# Motors.net
KiCad netlist of a schematic drawn in Altium Designer
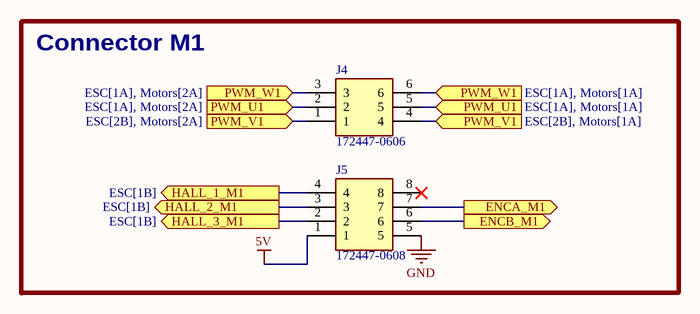
[diagram p0: Motors.SchDoc]

(export (version "E")
  (design (tool "Eeschema 10.0.6"))
  (components
    (comp (ref "J4")
      (value "172447-0606")
      (footprint "roboime:172447-YY06")
      (description "Connector")
      (fields (field (name "MOUSER PART NUMBER") "538-172447-0606"))
      (libsource (lib "roboime") (part "172447-0606"))
    )
    (comp (ref "J5")
      (value "172447-0608")
      (footprint "roboime:172447-YY08")
      (description "Connector Mate 46992-0840")
      (fields (field (name "MOUSER PART NUMBER") "538-172447-0608"))
      (libsource (lib "roboime") (part "172447-0608"))
    )
  )
  (nets
    (net (code "1") (name "/ENCA_M1") (class "Default")
      (node (ref "J5") (pin "7") (pinfunction "7_7") (pintype "passive"))
    )
    (net (code "2") (name "/ENCB_M1") (class "Default")
      (node (ref "J5") (pin "6") (pinfunction "6_6") (pintype "passive"))
    )
    (net (code "3") (name "/HALL_1_M1") (class "Default")
      (node (ref "J5") (pin "4") (pinfunction "4_4") (pintype "passive"))
    )
    (net (code "4") (name "/HALL_2_M1") (class "Default")
      (node (ref "J5") (pin "3") (pinfunction "3_3") (pintype "passive"))
    )
    (net (code "5") (name "/HALL_3_M1") (class "Default")
      (node (ref "J5") (pin "2") (pinfunction "2_2") (pintype "passive"))
    )
    (net (code "6") (name "/PWM_U1") (class "Default")
      (node (ref "J4") (pin "2") (pinfunction "2_2") (pintype "passive"))
      (node (ref "J4") (pin "5") (pinfunction "5_5") (pintype "passive"))
    )
    (net (code "7") (name "/PWM_V1") (class "Default")
      (node (ref "J4") (pin "1") (pinfunction "1_1") (pintype "passive"))
      (node (ref "J4") (pin "4") (pinfunction "4_4") (pintype "passive"))
    )
    (net (code "8") (name "/PWM_W1") (class "Default")
      (node (ref "J4") (pin "3") (pinfunction "3_3") (pintype "passive"))
      (node (ref "J4") (pin "6") (pinfunction "6_6") (pintype "passive"))
    )
    (net (code "9") (name "5V") (class "Default")
      (node (ref "J5") (pin "1") (pinfunction "1_1") (pintype "passive"))
    )
    (net (code "10") (name "GND") (class "Default")
      (node (ref "J5") (pin "5") (pinfunction "5_5") (pintype "passive"))
    )
    (net (code "11") (name "unconnected-(J5-Pad8)") (class "Default")
      (node (ref "J5") (pin "8") (pinfunction "8_8") (pintype "passive+no_connect"))
    )
  )
)
